# PIC_Prototyping_Schematic.net
KiCad netlist of a schematic drawn in Altium Designer
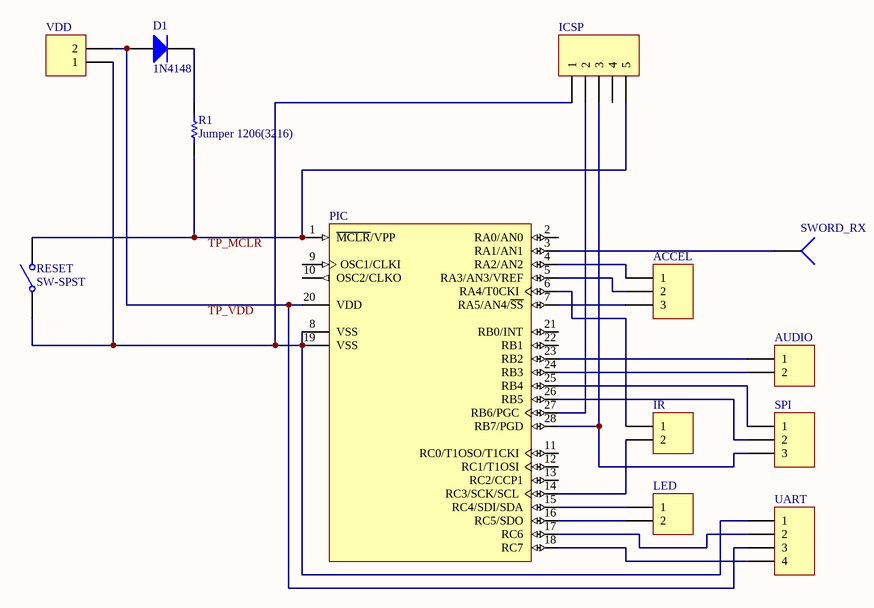
[diagram p0: PIC_Prototyping_Schematic.SchDoc]

(export (version "E")
  (design (tool "Eeschema 10.0.6"))
  (components
    (comp (ref "ACCEL")
      (value "Header 3")
      (footprint "HDR1X3")
      (description "Header, 3-Pin")
      (fields (field (name "PUBLISHER") "Altium Limited"))
      (libsource (lib "Miscellaneous Connectors") (part "Header 3"))
    )
    (comp (ref "AUDIO")
      (value "Header 2")
      (footprint "HDR1X2")
      (description "Header, 2-Pin")
      (fields (field (name "PUBLISHER") "Altium Limited"))
      (libsource (lib "Miscellaneous Connectors") (part "Header 2"))
    )
    (comp (ref "D1")
      (value "1N4148")
      (footprint "DO-35")
      (description "High Conductance Fast Diode")
      (fields (field (name "PUBLISHER") "Altium Limited"))
      (libsource (lib "FSC Discrete Diode") (part "1N4148"))
    )
    (comp (ref "ICSP")
      (value "Header 5")
      (footprint "HDR1X5")
      (description "Header, 5-Pin")
      (fields (field (name "PUBLISHER") "Altium Limited"))
      (libsource (lib "Miscellaneous Connectors") (part "Header 5"))
    )
    (comp (ref "IR")
      (value "Header 2")
      (footprint "HDR1X2")
      (description "Header, 2-Pin")
      (fields (field (name "PUBLISHER") "Altium Limited"))
      (libsource (lib "Miscellaneous Connectors") (part "Header 2"))
    )
    (comp (ref "LED")
      (value "Header 2")
      (footprint "HDR1X2")
      (description "Header, 2-Pin")
      (fields (field (name "PUBLISHER") "Altium Limited"))
      (libsource (lib "Miscellaneous Connectors") (part "Header 2"))
    )
    (comp (ref "PIC")
      (value "PIC16F72-I/SP")
      (footprint "SPDIP300-SP28")
      (fields (field (name "PUBLISHER") "Altium Limited"))
      (libsource (lib "Microchip Microcontroller 8-Bit PIC16") (part "PIC16F72-I/SP"))
    )
    (comp (ref "R1")
      (value "Jumper 1206(3216)")
      (footprint "RESC1206(3216)_L")
      (description "Jumper 1206 (3216 Metric)")
      (fields (field (name "TOLERANCE") "None"))
      (libsource (lib "Altium Content Vault") (part "RES"))
    )
    (comp (ref "RESET")
      (value "SW-SPST")
      (footprint "SPST-2")
      (description "Single-Pole, Single-Throw Switch")
      (fields (field (name "PUBLISHER") "Altium Limited"))
      (libsource (lib "Miscellaneous Devices") (part "SW-SPST"))
    )
    (comp (ref "SPI")
      (value "Header 3")
      (footprint "HDR1X3")
      (description "Header, 3-Pin")
      (fields (field (name "PUBLISHER") "Altium Limited"))
      (libsource (lib "Miscellaneous Connectors") (part "Header 3"))
    )
    (comp (ref "SWORD_RX")
      (value "Socket")
      (footprint "PIN1")
      (fields (field (name "PUBLISHER") "Altium Limited"))
      (libsource (lib "Miscellaneous Connectors") (part "Socket"))
    )
    (comp (ref "UART")
      (value "Header 4")
      (footprint "HDR1X4")
      (description "Header, 4-Pin")
      (fields (field (name "PUBLISHER") "Altium Limited"))
      (libsource (lib "Miscellaneous Connectors") (part "Header 4"))
    )
    (comp (ref "VDD")
      (value "Header 2")
      (footprint "HDR1X2")
      (description "Header, 2-Pin")
      (fields (field (name "PUBLISHER") "Altium Limited"))
      (libsource (lib "") (part "Header 2_1"))
    )
  )
  (nets
    (net (code "3") (name "Net-(D1-A)") (class "Default")
      (node (ref "D1") (pin "1") (pinfunction "A_1") (pintype "passive"))
      (node (ref "PIC") (pin "20") (pinfunction "VDD_20") (pintype "power_in"))
      (node (ref "UART") (pin "3") (pinfunction "3_3") (pintype "passive"))
      (node (ref "VDD") (pin "2") (pinfunction "2_2") (pintype "passive"))
    )
    (net (code "4") (name "Net-(D1-K)") (class "Default")
      (node (ref "D1") (pin "2") (pinfunction "K_2") (pintype "passive"))
      (node (ref "R1") (pin "2") (pinfunction "2_2") (pintype "passive"))
    )
    (net (code "5") (name "Net-(PIC-RA1{slash}AN1)") (class "Default")
      (node (ref "PIC") (pin "3") (pinfunction "RA1/AN1_3") (pintype "bidirectional"))
      (node (ref "SWORD_RX") (pin "1") (pinfunction "1_1") (pintype "passive"))
    )
    (net (code "6") (name "Net-(PIC-RA2{slash}AN2)") (class "Default")
      (node (ref "ACCEL") (pin "1") (pinfunction "1_1") (pintype "passive"))
      (node (ref "PIC") (pin "4") (pinfunction "RA2/AN2_4") (pintype "bidirectional"))
    )
    (net (code "7") (name "Net-(PIC-RA3{slash}AN3{slash}VREF)") (class "Default")
      (node (ref "ACCEL") (pin "2") (pinfunction "2_2") (pintype "passive"))
      (node (ref "PIC") (pin "5") (pinfunction "RA3/AN3/VREF_5") (pintype "bidirectional"))
    )
    (net (code "8") (name "Net-(PIC-RA4{slash}T0CKI)") (class "Default")
      (node (ref "IR") (pin "1") (pinfunction "1_1") (pintype "passive"))
      (node (ref "PIC") (pin "6") (pinfunction "RA4/T0CKI_6") (pintype "bidirectional"))
    )
    (net (code "9") (name "Net-(PIC-RA5{slash}AN4{slash}~{SS})") (class "Default")
      (node (ref "ACCEL") (pin "3") (pinfunction "3_3") (pintype "passive"))
      (node (ref "PIC") (pin "7") (pinfunction "RA5/AN4/~{SS}_7") (pintype "bidirectional"))
    )
    (net (code "10") (name "Net-(PIC-RB2)") (class "Default")
      (node (ref "AUDIO") (pin "1") (pinfunction "1_1") (pintype "passive"))
      (node (ref "PIC") (pin "23") (pinfunction "RB2_23") (pintype "bidirectional"))
    )
    (net (code "11") (name "Net-(PIC-RB3)") (class "Default")
      (node (ref "AUDIO") (pin "2") (pinfunction "2_2") (pintype "passive"))
      (node (ref "PIC") (pin "24") (pinfunction "RB3_24") (pintype "bidirectional"))
    )
    (net (code "12") (name "Net-(PIC-RB4)") (class "Default")
      (node (ref "PIC") (pin "25") (pinfunction "RB4_25") (pintype "bidirectional"))
      (node (ref "SPI") (pin "1") (pinfunction "1_1") (pintype "passive"))
    )
    (net (code "13") (name "Net-(PIC-RB5)") (class "Default")
      (node (ref "PIC") (pin "26") (pinfunction "RB5_26") (pintype "bidirectional"))
      (node (ref "SPI") (pin "2") (pinfunction "2_2") (pintype "passive"))
    )
    (net (code "14") (name "Net-(PIC-RB6{slash}PGC)") (class "Default")
      (node (ref "ICSP") (pin "2") (pinfunction "2_2") (pintype "passive"))
      (node (ref "PIC") (pin "27") (pinfunction "RB6/PGC_27") (pintype "bidirectional"))
    )
    (net (code "15") (name "Net-(PIC-RB7{slash}PGD)") (class "Default")
      (node (ref "ICSP") (pin "3") (pinfunction "3_3") (pintype "passive"))
      (node (ref "PIC") (pin "28") (pinfunction "RB7/PGD_28") (pintype "bidirectional"))
      (node (ref "SPI") (pin "3") (pinfunction "3_3") (pintype "passive"))
    )
    (net (code "16") (name "Net-(PIC-RC3{slash}SCK{slash}SCL)") (class "Default")
      (node (ref "IR") (pin "2") (pinfunction "2_2") (pintype "passive"))
      (node (ref "PIC") (pin "14") (pinfunction "RC3/SCK/SCL_14") (pintype "bidirectional"))
    )
    (net (code "17") (name "Net-(PIC-RC4{slash}SDI{slash}SDA)") (class "Default")
      (node (ref "LED") (pin "1") (pinfunction "1_1") (pintype "passive"))
      (node (ref "PIC") (pin "15") (pinfunction "RC4/SDI/SDA_15") (pintype "bidirectional"))
    )
    (net (code "18") (name "Net-(PIC-RC5{slash}SDO)") (class "Default")
      (node (ref "LED") (pin "2") (pinfunction "2_2") (pintype "passive"))
      (node (ref "PIC") (pin "16") (pinfunction "RC5/SDO_16") (pintype "bidirectional"))
    )
    (net (code "19") (name "Net-(PIC-RC6)") (class "Default")
      (node (ref "PIC") (pin "17") (pinfunction "RC6_17") (pintype "bidirectional"))
      (node (ref "UART") (pin "2") (pinfunction "2_2") (pintype "passive"))
    )
    (net (code "20") (name "Net-(PIC-RC7)") (class "Default")
      (node (ref "PIC") (pin "18") (pinfunction "RC7_18") (pintype "bidirectional"))
      (node (ref "UART") (pin "4") (pinfunction "4_4") (pintype "passive"))
    )
    (net (code "21") (name "Net-(PIC-~{MCLR}{slash}VPP)") (class "Default")
      (node (ref "ICSP") (pin "5") (pinfunction "5_5") (pintype "passive"))
      (node (ref "PIC") (pin "1") (pinfunction "~{MCLR}/VPP_1") (pintype "input"))
      (node (ref "R1") (pin "1") (pinfunction "1_1") (pintype "passive"))
      (node (ref "RESET") (pin "2") (pinfunction "NO_2") (pintype "passive"))
    )
    (net (code "22") (name "Net-(RESET-COMMON)") (class "Default")
      (node (ref "ICSP") (pin "1") (pinfunction "1_1") (pintype "passive"))
      (node (ref "PIC") (pin "19") (pinfunction "VSS_19") (pintype "power_in"))
      (node (ref "PIC") (pin "8") (pinfunction "VSS_8") (pintype "power_in"))
      (node (ref "RESET") (pin "1") (pinfunction "COMMON_1") (pintype "passive"))
      (node (ref "UART") (pin "1") (pinfunction "1_1") (pintype "passive"))
      (node (ref "VDD") (pin "1") (pinfunction "1_1") (pintype "passive"))
    )
    (net (code "23") (name "unconnected-(ICSP-Pad4)") (class "Default")
      (node (ref "ICSP") (pin "4") (pinfunction "4_4") (pintype "passive"))
    )
    (net (code "24") (name "unconnected-(PIC-OSC1{slash}CLKI-Pad9)") (class "Default")
      (node (ref "PIC") (pin "9") (pinfunction "OSC1/CLKI_9") (pintype "input"))
    )
    (net (code "25") (name "unconnected-(PIC-OSC2{slash}CLKO-Pad10)") (class "Default")
      (node (ref "PIC") (pin "10") (pinfunction "OSC2/CLKO_10") (pintype "output"))
    )
    (net (code "26") (name "unconnected-(PIC-RA0{slash}AN0-Pad2)") (class "Default")
      (node (ref "PIC") (pin "2") (pinfunction "RA0/AN0_2") (pintype "bidirectional"))
    )
    (net (code "27") (name "unconnected-(PIC-RB0{slash}INT-Pad21)") (class "Default")
      (node (ref "PIC") (pin "21") (pinfunction "RB0/INT_21") (pintype "bidirectional"))
    )
    (net (code "28") (name "unconnected-(PIC-RB1-Pad22)") (class "Default")
      (node (ref "PIC") (pin "22") (pinfunction "RB1_22") (pintype "bidirectional"))
    )
    (net (code "29") (name "unconnected-(PIC-RC0{slash}T1OSO{slash}T1CKI-Pad11)") (class "Default")
      (node (ref "PIC") (pin "11") (pinfunction "RC0/T1OSO/T1CKI_11") (pintype "bidirectional"))
    )
    (net (code "30") (name "unconnected-(PIC-RC1{slash}T1OSI-Pad12)") (class "Default")
      (node (ref "PIC") (pin "12") (pinfunction "RC1/T1OSI_12") (pintype "bidirectional"))
    )
    (net (code "31") (name "unconnected-(PIC-RC2{slash}CCP1-Pad13)") (class "Default")
      (node (ref "PIC") (pin "13") (pinfunction "RC2/CCP1_13") (pintype "bidirectional"))
    )
  )
)
